# PCI_Express_16765X6890_36PIN_Half_length.net
KiCad netlist of a schematic drawn in Altium Designer
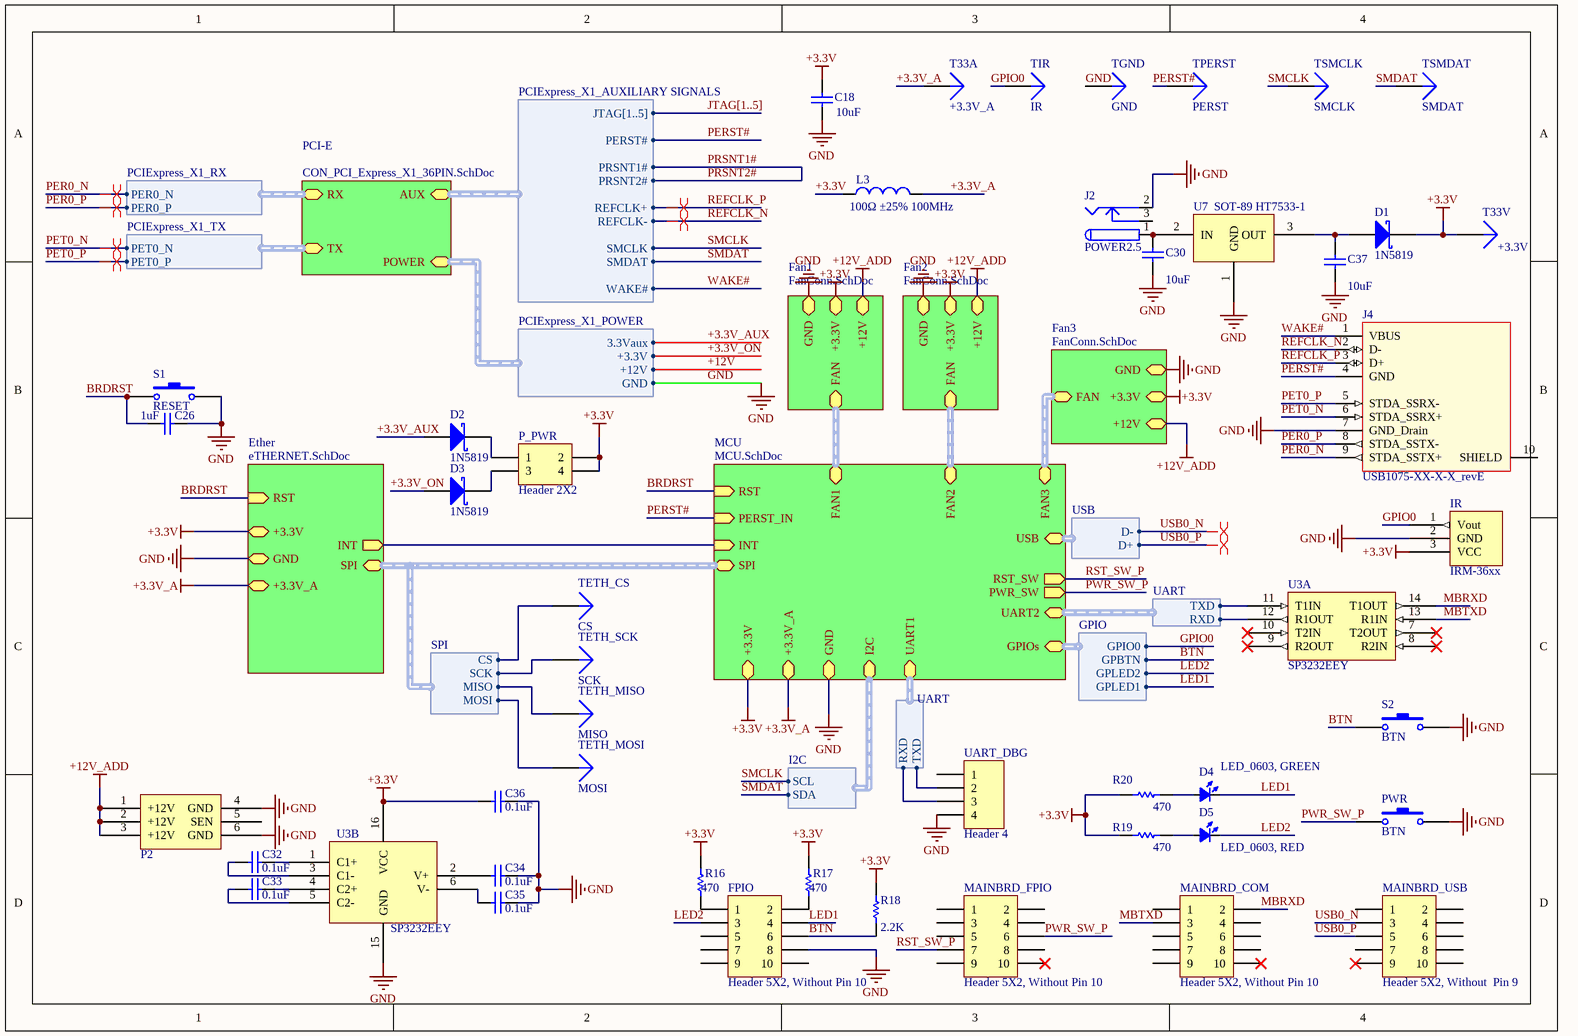
[diagram p0: PCI Express_16765X6890_36PIN_Half length.schdoc]

(export (version "E")
  (design (tool "Eeschema 10.0.6"))
  (components
    (comp (ref "C18")
      (value "10uF")
      (footprint "C-1608[0603]")
      (description "Capacitor (Semiconductor SIM Model)")
      (fields (field (name "PUBLISHER") "Altium Limited"))
      (libsource (lib "Miscellaneous Devices") (part "Cap Semi"))
    )
    (comp (ref "C26")
      (value "1uF")
      (footprint "C-1608[0603]")
      (description "Capacitor (Semiconductor SIM Model)")
      (fields (field (name "Comment") "Cap Semi") (field (name "PUBLISHER") "Altium Limited"))
      (libsource (lib "Miscellaneous Devices") (part "Cap Semi"))
    )
    (comp (ref "C30")
      (value "10uF")
      (footprint "C-1608[0603]")
      (description "Capacitor (Semiconductor SIM Model)")
      (fields (field (name "PUBLISHER") "Altium Limited"))
      (libsource (lib "Miscellaneous Devices") (part "Cap Semi"))
    )
    (comp (ref "C32")
      (value "0.1uF")
      (footprint "C-1608[0603]")
      (description "Capacitor (Semiconductor SIM Model)")
      (fields (field (name "PUBLISHER") "Altium Limited"))
      (libsource (lib "Miscellaneous Devices") (part "Cap Semi"))
    )
    (comp (ref "C33")
      (value "0.1uF")
      (footprint "C-1608[0603]")
      (description "Capacitor (Semiconductor SIM Model)")
      (fields (field (name "PUBLISHER") "Altium Limited"))
      (libsource (lib "Miscellaneous Devices") (part "Cap Semi"))
    )
    (comp (ref "C34")
      (value "0.1uF")
      (footprint "C-1608[0603]")
      (description "Capacitor (Semiconductor SIM Model)")
      (fields (field (name "PUBLISHER") "Altium Limited"))
      (libsource (lib "Miscellaneous Devices") (part "Cap Semi"))
    )
    (comp (ref "C35")
      (value "0.1uF")
      (footprint "C-1608[0603]")
      (description "Capacitor (Semiconductor SIM Model)")
      (fields (field (name "PUBLISHER") "Altium Limited"))
      (libsource (lib "Miscellaneous Devices") (part "Cap Semi"))
    )
    (comp (ref "C36")
      (value "0.1uF")
      (footprint "C-1608[0603]")
      (description "Capacitor (Semiconductor SIM Model)")
      (fields (field (name "PUBLISHER") "Altium Limited"))
      (libsource (lib "Miscellaneous Devices") (part "Cap Semi"))
    )
    (comp (ref "C37")
      (value "10uF")
      (footprint "C-1608[0603]")
      (description "Capacitor (Semiconductor SIM Model)")
      (fields (field (name "PUBLISHER") "Altium Limited"))
      (libsource (lib "Miscellaneous Devices") (part "Cap Semi"))
    )
    (comp (ref "D1")
      (value "1N5819")
      (footprint "SOD123")
      (description "Schottky Diode")
      (fields (field (name "PUBLISHER") "Altium Limited"))
      (libsource (lib "Miscellaneous Devices") (part "D Schottky"))
    )
    (comp (ref "D2")
      (value "1N5819")
      (footprint "SOD123")
      (description "Schottky Diode")
      (fields (field (name "PUBLISHER") "Altium Limited"))
      (libsource (lib "Miscellaneous Devices") (part "D Schottky"))
    )
    (comp (ref "D3")
      (value "1N5819")
      (footprint "SOD123")
      (description "Schottky Diode")
      (fields (field (name "PUBLISHER") "Altium Limited"))
      (libsource (lib "Miscellaneous Devices") (part "D Schottky"))
    )
    (comp (ref "D4")
      (value "LED_0603, GREEN")
      (footprint "PCB_ActiveLED:LED_0603_GREEN")
      (description "LED")
      (libsource (lib "SCH_Active") (part "LED_0603"))
    )
    (comp (ref "D5")
      (value "LED_0603, RED")
      (footprint "PCB_ActiveLED:LED_0603_RED")
      (description "LED")
      (libsource (lib "SCH_Active") (part "LED_0603"))
    )
    (comp (ref "FPIO")
      (value "Header 5X2, Without Pin 10")
      (footprint "HDR2X5-10")
      (description "Header, 5-Pin, Dual row")
      (fields (field (name "PUBLISHER") "Altium Limited"))
      (libsource (lib "Miscellaneous Connectors") (part "Header 5X2"))
    )
    (comp (ref "IR") (value "IRM-36xx") (footprint "IRM-36xx") (libsource (lib "general") (part "IRM-36xx")))
    (comp (ref "J2") (value "POWER2.5") (footprint "DC_POWER") (libsource (lib "general") (part "POWER2.5")))
    (comp (ref "J4")
      (value "USB1075-XX-X-X_revE")
      (footprint "USB1075-XX-X-X_revE")
      (description "USB 3.0 Receptecal, Type A, 9 Pin, Through Hole, Horizontal, Top Mount, with Kinked Shell Stakes")
      (libsource (lib "general") (part "USB1075-XX-X-X_revE"))
    )
    (comp (ref "L3")
      (value "100Ω ±25% 100MHz")
      (footprint "L-1608[0603]")
      (description "Inductor")
      (fields (field (name "PUBLISHER") "Altium Limited"))
      (libsource (lib "Miscellaneous Devices") (part "Inductor"))
    )
    (comp (ref "MAINBRD_COM")
      (value "Header 5X2, Without Pin 10")
      (footprint "HDR2X5-10")
      (description "Header, 5-Pin, Dual row")
      (fields (field (name "PUBLISHER") "Altium Limited"))
      (libsource (lib "Miscellaneous Connectors") (part "Header 5X2"))
    )
    (comp (ref "MAINBRD_FPIO")
      (value "Header 5X2, Without Pin 10")
      (footprint "HDR2X5-10")
      (description "Header, 5-Pin, Dual row")
      (fields (field (name "PUBLISHER") "Altium Limited"))
      (libsource (lib "Miscellaneous Connectors") (part "Header 5X2"))
    )
    (comp (ref "MAINBRD_USB")
      (value "Header 5X2, Without  Pin 9")
      (footprint "HDR2X5-9")
      (description "Header, 5-Pin, Dual row")
      (fields (field (name "PUBLISHER") "Altium Limited"))
      (libsource (lib "Miscellaneous Connectors") (part "Header 5X2"))
    )
    (comp (ref "P2")
      (value "PCI-E Aux Power Connector 6Pin")
      (footprint "PCIE_AUX_PWR_CONN_6P")
      (libsource (lib "general") (part "PCI-E Aux Power Connector 6Pin"))
    )
    (comp (ref "PWR")
      (value "BTN")
      (footprint "SW-SIDE")
      (description "Switch")
      (fields (field (name "PUBLISHER") "Altium Limited"))
      (libsource (lib "Miscellaneous Devices") (part "SW-PB"))
    )
    (comp (ref "P_PWR")
      (value "Header 2X2")
      (footprint "HDR2X2")
      (description "Header, 2-Pin, Dual row")
      (fields (field (name "PUBLISHER") "Altium Limited"))
      (libsource (lib "Miscellaneous Connectors") (part "Header 2X2"))
    )
    (comp (ref "R16")
      (value "470")
      (footprint "R-1608[0603]")
      (description "Semiconductor Resistor")
      (fields (field (name "PUBLISHER") "Altium Limited"))
      (libsource (lib "Miscellaneous Devices") (part "Res Semi"))
    )
    (comp (ref "R17")
      (value "470")
      (footprint "R-1608[0603]")
      (description "Semiconductor Resistor")
      (fields (field (name "PUBLISHER") "Altium Limited"))
      (libsource (lib "Miscellaneous Devices") (part "Res Semi"))
    )
    (comp (ref "R18")
      (value "2.2K")
      (footprint "R-1608[0603]")
      (description "Semiconductor Resistor")
      (fields (field (name "PUBLISHER") "Altium Limited"))
      (libsource (lib "Miscellaneous Devices") (part "Res Semi"))
    )
    (comp (ref "R19")
      (value "470")
      (footprint "R-1608[0603]")
      (description "Semiconductor Resistor")
      (fields (field (name "PUBLISHER") "Altium Limited"))
      (libsource (lib "Miscellaneous Devices") (part "Res Semi"))
    )
    (comp (ref "R20")
      (value "470")
      (footprint "R-1608[0603]")
      (description "Semiconductor Resistor")
      (fields (field (name "PUBLISHER") "Altium Limited"))
      (libsource (lib "Miscellaneous Devices") (part "Res Semi"))
    )
    (comp (ref "S1")
      (value "RESET")
      (footprint "SW-2pin-SMD")
      (description "Switch")
      (fields (field (name "PUBLISHER") "Altium Limited"))
      (libsource (lib "Miscellaneous Devices") (part "SW-PB"))
    )
    (comp (ref "S2")
      (value "BTN")
      (footprint "SW-SIDE")
      (description "Switch")
      (fields (field (name "PUBLISHER") "Altium Limited"))
      (libsource (lib "Miscellaneous Devices") (part "SW-PB"))
    )
    (comp (ref "T33A")
      (value "+3.3V_A")
      (footprint "general:TESTPOINT")
      (description "Plug")
      (fields (field (name "PUBLISHER") "Altium Limited"))
      (libsource (lib "Miscellaneous Connectors") (part "Plug"))
    )
    (comp (ref "T33V")
      (value "+3.3V")
      (footprint "general:TESTPOINT")
      (description "Plug")
      (fields (field (name "PUBLISHER") "Altium Limited"))
      (libsource (lib "Miscellaneous Connectors") (part "Plug"))
    )
    (comp (ref "TETH_CS")
      (value "CS")
      (footprint "general:TESTPOINT")
      (description "Plug")
      (fields (field (name "PUBLISHER") "Altium Limited"))
      (libsource (lib "Miscellaneous Connectors") (part "Plug"))
    )
    (comp (ref "TETH_MISO")
      (value "MISO")
      (footprint "general:TESTPOINT")
      (description "Plug")
      (fields (field (name "PUBLISHER") "Altium Limited"))
      (libsource (lib "Miscellaneous Connectors") (part "Plug"))
    )
    (comp (ref "TETH_MOSI")
      (value "MOSI")
      (footprint "general:TESTPOINT")
      (description "Plug")
      (fields (field (name "PUBLISHER") "Altium Limited"))
      (libsource (lib "Miscellaneous Connectors") (part "Plug"))
    )
    (comp (ref "TETH_SCK")
      (value "SCK")
      (footprint "general:TESTPOINT")
      (description "Plug")
      (fields (field (name "PUBLISHER") "Altium Limited"))
      (libsource (lib "Miscellaneous Connectors") (part "Plug"))
    )
    (comp (ref "TGND")
      (value "GND")
      (footprint "general:TESTPOINT")
      (description "Plug")
      (fields (field (name "PUBLISHER") "Altium Limited"))
      (libsource (lib "Miscellaneous Connectors") (part "Plug"))
    )
    (comp (ref "TIR")
      (value "IR")
      (footprint "general:TESTPOINT")
      (description "Plug")
      (fields (field (name "PUBLISHER") "Altium Limited"))
      (libsource (lib "Miscellaneous Connectors") (part "Plug"))
    )
    (comp (ref "TPERST")
      (value "PERST")
      (footprint "general:TESTPOINT")
      (description "Plug")
      (fields (field (name "PUBLISHER") "Altium Limited"))
      (libsource (lib "Miscellaneous Connectors") (part "Plug"))
    )
    (comp (ref "TSMCLK")
      (value "SMCLK")
      (footprint "general:TESTPOINT")
      (description "Plug")
      (fields (field (name "PUBLISHER") "Altium Limited"))
      (libsource (lib "Miscellaneous Connectors") (part "Plug"))
    )
    (comp (ref "TSMDAT")
      (value "SMDAT")
      (footprint "general:TESTPOINT")
      (description "Plug")
      (fields (field (name "PUBLISHER") "Altium Limited"))
      (libsource (lib "Miscellaneous Connectors") (part "Plug"))
    )
    (comp (ref "U3")
      (value "SP3232EEY")
      (footprint "LC-TSSOP-16")
      (libsource (lib "general") (part "SP3232EEY"))
    )
    (comp (ref "U7")
      (value "SOT-89 HT7533-1")
      (footprint "SOT89")
      (description "Low Power Consumption LDO")
      (libsource (lib "general") (part "HT73XX"))
    )
    (comp (ref "UART_DBG")
      (value "Header 4")
      (footprint "HDR1X4")
      (description "Header, 4-Pin")
      (fields (field (name "PUBLISHER") "Altium Limited"))
      (libsource (lib "Miscellaneous Connectors") (part "Header 4"))
    )
  )
  (nets
    (net (code "10") (name "+3.3V") (class "Default")
      (node (ref "C18") (pin "2") (pinfunction "2_2") (pintype "passive"))
      (node (ref "C36") (pin "2") (pinfunction "2_2") (pintype "passive"))
      (node (ref "D1") (pin "2") (pinfunction "K_2") (pintype "passive"))
      (node (ref "IR") (pin "3") (pinfunction "VCC_3") (pintype "power_in"))
      (node (ref "L3") (pin "1") (pinfunction "1_1") (pintype "passive"))
      (node (ref "P_PWR") (pin "2") (pinfunction "2_2") (pintype "passive"))
      (node (ref "P_PWR") (pin "4") (pinfunction "4_4") (pintype "passive"))
      (node (ref "R16") (pin "2") (pinfunction "2_2") (pintype "passive"))
      (node (ref "R17") (pin "2") (pinfunction "2_2") (pintype "passive"))
      (node (ref "R18") (pin "2") (pinfunction "2_2") (pintype "passive"))
      (node (ref "R19") (pin "2") (pinfunction "2_2") (pintype "passive"))
      (node (ref "R20") (pin "2") (pinfunction "2_2") (pintype "passive"))
      (node (ref "T33V") (pin "1") (pinfunction "1_1") (pintype "passive"))
      (node (ref "U3") (pin "16") (pinfunction "VCC_16") (pintype "power_in"))
    )
    (net (code "11") (name "+3.3V_A") (class "Default")
      (node (ref "L3") (pin "2") (pinfunction "2_2") (pintype "passive"))
      (node (ref "T33A") (pin "1") (pinfunction "1_1") (pintype "passive"))
    )
    (net (code "12") (name "+12V_ADD") (class "Default")
      (node (ref "P2") (pin "1") (pinfunction "+12V_1") (pintype "power_in"))
      (node (ref "P2") (pin "2") (pinfunction "+12V_2") (pintype "power_in"))
      (node (ref "P2") (pin "3") (pinfunction "+12V_3") (pintype "power_in"))
    )
    (net (code "13") (name "/+3.3V_AUX") (class "Default")
      (node (ref "D2") (pin "1") (pinfunction "A_1") (pintype "passive"))
    )
    (net (code "14") (name "/+3.3V_ON") (class "Default")
      (node (ref "D3") (pin "1") (pinfunction "A_1") (pintype "passive"))
    )
    (net (code "17") (name "/BRDRST") (class "Default")
      (node (ref "C26") (pin "1") (pinfunction "1_1") (pintype "passive"))
      (node (ref "S1") (pin "1") (pinfunction "1_1") (pintype "passive"))
    )
    (net (code "18") (name "/BTN") (class "Default")
      (node (ref "FPIO") (pin "6") (pinfunction "6_6") (pintype "passive"))
      (node (ref "R18") (pin "1") (pinfunction "1_1") (pintype "passive"))
      (node (ref "S2") (pin "1") (pinfunction "1_1") (pintype "passive"))
    )
    (net (code "19") (name "/CS") (class "Default")
      (node (ref "TETH_CS") (pin "1") (pinfunction "1_1") (pintype "passive"))
    )
    (net (code "23") (name "/GPIO0") (class "Default")
      (node (ref "IR") (pin "1") (pinfunction "Vout_1") (pintype "output"))
      (node (ref "TIR") (pin "1") (pinfunction "1_1") (pintype "passive"))
    )
    (net (code "25") (name "/LED1") (class "Default")
      (node (ref "D4") (pin "2") (pinfunction "K_2") (pintype "passive"))
      (node (ref "FPIO") (pin "4") (pinfunction "4_4") (pintype "passive"))
    )
    (net (code "26") (name "/LED2") (class "Default")
      (node (ref "D5") (pin "2") (pinfunction "K_2") (pintype "passive"))
      (node (ref "FPIO") (pin "3") (pinfunction "3_3") (pintype "passive"))
    )
    (net (code "27") (name "/MBRXD") (class "Default")
      (node (ref "MAINBRD_COM") (pin "2") (pinfunction "2_2") (pintype "passive"))
      (node (ref "U3") (pin "14") (pinfunction "T1OUT_14") (pintype "output"))
    )
    (net (code "28") (name "/MBTXD") (class "Default")
      (node (ref "MAINBRD_COM") (pin "3") (pinfunction "3_3") (pintype "passive"))
      (node (ref "U3") (pin "13") (pinfunction "R1IN_13") (pintype "input"))
    )
    (net (code "29") (name "/MISO") (class "Default")
      (node (ref "TETH_MISO") (pin "1") (pinfunction "1_1") (pintype "passive"))
    )
    (net (code "30") (name "/MOSI") (class "Default")
      (node (ref "TETH_MOSI") (pin "1") (pinfunction "1_1") (pintype "passive"))
    )
    (net (code "31") (name "/PER0_N") (class "Default")
      (node (ref "J4") (pin "9") (pinfunction "STDA_SSTX+_9") (pintype "output"))
    )
    (net (code "32") (name "/PER0_P") (class "Default")
      (node (ref "J4") (pin "8") (pinfunction "STDA_SSTX-_8") (pintype "output"))
    )
    (net (code "33") (name "/PERST#") (class "Default")
      (node (ref "J4") (pin "4") (pinfunction "GND_4") (pintype "power_in"))
      (node (ref "TPERST") (pin "1") (pinfunction "1_1") (pintype "passive"))
    )
    (net (code "34") (name "/PET0_N") (class "Default")
      (node (ref "J4") (pin "6") (pinfunction "STDA_SSRX+_6") (pintype "input"))
    )
    (net (code "35") (name "/PET0_P") (class "Default")
      (node (ref "J4") (pin "5") (pinfunction "STDA_SSRX-_5") (pintype "input"))
    )
    (net (code "37") (name "/PWR_SW_P") (class "Default")
      (node (ref "MAINBRD_FPIO") (pin "6") (pinfunction "6_6") (pintype "passive"))
      (node (ref "PWR") (pin "1") (pinfunction "1_1") (pintype "passive"))
    )
    (net (code "38") (name "/REFCLK_N") (class "Default")
      (node (ref "J4") (pin "2") (pinfunction "D-_2") (pintype "bidirectional"))
    )
    (net (code "39") (name "/REFCLK_P") (class "Default")
      (node (ref "J4") (pin "3") (pinfunction "D+_3") (pintype "bidirectional"))
    )
    (net (code "40") (name "/RST_SW_P") (class "Default")
      (node (ref "MAINBRD_FPIO") (pin "7") (pinfunction "7_7") (pintype "passive"))
    )
    (net (code "41") (name "/SCK") (class "Default")
      (node (ref "TETH_SCK") (pin "1") (pinfunction "1_1") (pintype "passive"))
    )
    (net (code "42") (name "/SMCLK") (class "Default")
      (node (ref "TSMCLK") (pin "1") (pinfunction "1_1") (pintype "passive"))
    )
    (net (code "43") (name "/SMDAT") (class "Default")
      (node (ref "TSMDAT") (pin "1") (pinfunction "1_1") (pintype "passive"))
    )
    (net (code "45") (name "/USB0_N") (class "Default")
      (node (ref "MAINBRD_USB") (pin "3") (pinfunction "3_3") (pintype "passive"))
    )
    (net (code "46") (name "/USB0_P") (class "Default")
      (node (ref "MAINBRD_USB") (pin "5") (pinfunction "5_5") (pintype "passive"))
    )
    (net (code "47") (name "/WAKE#") (class "Default")
      (node (ref "J4") (pin "1") (pinfunction "VBUS_1") (pintype "power_in"))
    )
    (net (code "57") (name "GND") (class "Default")
      (node (ref "C18") (pin "1") (pinfunction "1_1") (pintype "passive"))
      (node (ref "C26") (pin "2") (pinfunction "2_2") (pintype "passive"))
      (node (ref "C30") (pin "1") (pinfunction "1_1") (pintype "passive"))
      (node (ref "C34") (pin "1") (pinfunction "1_1") (pintype "passive"))
      (node (ref "C35") (pin "1") (pinfunction "1_1") (pintype "passive"))
      (node (ref "C36") (pin "1") (pinfunction "1_1") (pintype "passive"))
      (node (ref "C37") (pin "1") (pinfunction "1_1") (pintype "passive"))
      (node (ref "FPIO") (pin "8") (pinfunction "8_8") (pintype "passive"))
      (node (ref "IR") (pin "2") (pinfunction "GND_2") (pintype "power_in"))
      (node (ref "J2") (pin "2") (pintype "passive"))
      (node (ref "J4") (pin "7") (pinfunction "GND_Drain_7") (pintype "power_in"))
      (node (ref "P2") (pin "4") (pinfunction "GND_4") (pintype "power_in"))
      (node (ref "P2") (pin "6") (pinfunction "GND_6") (pintype "power_in"))
      (node (ref "PWR") (pin "2") (pinfunction "2_2") (pintype "passive"))
      (node (ref "S1") (pin "2") (pinfunction "2_2") (pintype "passive"))
      (node (ref "S2") (pin "2") (pinfunction "2_2") (pintype "passive"))
      (node (ref "TGND") (pin "1") (pinfunction "1_1") (pintype "passive"))
      (node (ref "U3") (pin "15") (pinfunction "GND_15") (pintype "power_in"))
      (node (ref "U7") (pin "1") (pinfunction "GND_1") (pintype "passive"))
      (node (ref "UART_DBG") (pin "4") (pinfunction "4_4") (pintype "passive"))
    )
    (net (code "58") (name "Net-(D1-A)") (class "Default")
      (node (ref "C37") (pin "2") (pinfunction "2_2") (pintype "passive"))
      (node (ref "D1") (pin "1") (pinfunction "A_1") (pintype "passive"))
      (node (ref "U7") (pin "3") (pinfunction "OUT_3") (pintype "passive"))
    )
    (net (code "59") (name "Net-(D2-K)") (class "Default")
      (node (ref "D2") (pin "2") (pinfunction "K_2") (pintype "passive"))
      (node (ref "P_PWR") (pin "1") (pinfunction "1_1") (pintype "passive"))
    )
    (net (code "60") (name "Net-(D3-K)") (class "Default")
      (node (ref "D3") (pin "2") (pinfunction "K_2") (pintype "passive"))
      (node (ref "P_PWR") (pin "3") (pinfunction "3_3") (pintype "passive"))
    )
    (net (code "61") (name "Net-(D4-A)") (class "Default")
      (node (ref "D4") (pin "1") (pinfunction "A_1") (pintype "passive"))
      (node (ref "R20") (pin "1") (pinfunction "1_1") (pintype "passive"))
    )
    (net (code "62") (name "Net-(D5-A)") (class "Default")
      (node (ref "D5") (pin "1") (pinfunction "A_1") (pintype "passive"))
      (node (ref "R19") (pin "1") (pinfunction "1_1") (pintype "passive"))
    )
    (net (code "63") (name "Net-(FPIO-Pad1)") (class "Default")
      (node (ref "FPIO") (pin "1") (pinfunction "1_1") (pintype "passive"))
      (node (ref "R16") (pin "1") (pinfunction "1_1") (pintype "passive"))
    )
    (net (code "64") (name "Net-(FPIO-Pad2)") (class "Default")
      (node (ref "FPIO") (pin "2") (pinfunction "2_2") (pintype "passive"))
      (node (ref "R17") (pin "1") (pinfunction "1_1") (pintype "passive"))
    )
    (net (code "65") (name "Net-(U3B-C1+)") (class "Default")
      (node (ref "C32") (pin "1") (pinfunction "1_1") (pintype "passive"))
      (node (ref "U3") (pin "1") (pinfunction "C1+_1") (pintype "power_in"))
    )
    (net (code "66") (name "Net-(U3B-C1-)") (class "Default")
      (node (ref "C32") (pin "2") (pinfunction "2_2") (pintype "passive"))
      (node (ref "U3") (pin "3") (pinfunction "C1-_3") (pintype "power_in"))
    )
    (net (code "67") (name "Net-(U3B-C2+)") (class "Default")
      (node (ref "C33") (pin "1") (pinfunction "1_1") (pintype "passive"))
      (node (ref "U3") (pin "4") (pinfunction "C2+_4") (pintype "power_in"))
    )
    (net (code "68") (name "Net-(U3B-C2-)") (class "Default")
      (node (ref "C33") (pin "2") (pinfunction "2_2") (pintype "passive"))
      (node (ref "U3") (pin "5") (pinfunction "C2-_5") (pintype "power_in"))
    )
    (net (code "69") (name "Net-(U3B-V+)") (class "Default")
      (node (ref "C34") (pin "2") (pinfunction "2_2") (pintype "passive"))
      (node (ref "U3") (pin "2") (pinfunction "V+_2") (pintype "power_in"))
    )
    (net (code "70") (name "Net-(U3B-V-)") (class "Default")
      (node (ref "C35") (pin "2") (pinfunction "2_2") (pintype "passive"))
      (node (ref "U3") (pin "6") (pinfunction "V-_6") (pintype "power_in"))
    )
    (net (code "71") (name "Net-(U7-IN)") (class "Default")
      (node (ref "C30") (pin "2") (pinfunction "2_2") (pintype "passive"))
      (node (ref "J2") (pin "1") (pintype "passive"))
      (node (ref "U7") (pin "2") (pinfunction "IN_2") (pintype "passive"))
    )
    (net (code "72") (name "unconnected-(FPIO-Pad5)") (class "Default")
      (node (ref "FPIO") (pin "5") (pinfunction "5_5") (pintype "passive"))
    )
    (net (code "73") (name "unconnected-(FPIO-Pad7)") (class "Default")
      (node (ref "FPIO") (pin "7") (pinfunction "7_7") (pintype "passive"))
    )
    (net (code "74") (name "unconnected-(FPIO-Pad9)") (class "Default")
      (node (ref "FPIO") (pin "9") (pinfunction "9_9") (pintype "passive"))
    )
    (net (code "75") (name "unconnected-(FPIO-Pad10)") (class "Default")
      (node (ref "FPIO") (pin "10") (pinfunction "10_10") (pintype "passive"))
    )
    (net (code "76") (name "unconnected-(J2-Pad3)") (class "Default")
      (node (ref "J2") (pin "3") (pintype "passive"))
    )
    (net (code "77") (name "unconnected-(J4-SHIELD-Pad10)") (class "Default")
      (node (ref "J4") (pin "10") (pinfunction "SHIELD_10") (pintype "passive"))
    )
    (net (code "78") (name "unconnected-(MAINBRD_COM-Pad1)") (class "Default")
      (node (ref "MAINBRD_COM") (pin "1") (pinfunction "1_1") (pintype "passive"))
    )
    (net (code "79") (name "unconnected-(MAINBRD_COM-Pad4)") (class "Default")
      (node (ref "MAINBRD_COM") (pin "4") (pinfunction "4_4") (pintype "passive"))
    )
    (net (code "80") (name "unconnected-(MAINBRD_COM-Pad5)") (class "Default")
      (node (ref "MAINBRD_COM") (pin "5") (pinfunction "5_5") (pintype "passive"))
    )
    (net (code "81") (name "unconnected-(MAINBRD_COM-Pad6)") (class "Default")
      (node (ref "MAINBRD_COM") (pin "6") (pinfunction "6_6") (pintype "passive"))
    )
    (net (code "82") (name "unconnected-(MAINBRD_COM-Pad7)") (class "Default")
      (node (ref "MAINBRD_COM") (pin "7") (pinfunction "7_7") (pintype "passive"))
    )
    (net (code "83") (name "unconnected-(MAINBRD_COM-Pad8)") (class "Default")
      (node (ref "MAINBRD_COM") (pin "8") (pinfunction "8_8") (pintype "passive"))
    )
    (net (code "84") (name "unconnected-(MAINBRD_COM-Pad9)") (class "Default")
      (node (ref "MAINBRD_COM") (pin "9") (pinfunction "9_9") (pintype "passive"))
    )
    (net (code "85") (name "unconnected-(MAINBRD_COM-Pad10)") (class "Default")
      (node (ref "MAINBRD_COM") (pin "10") (pinfunction "10_10") (pintype "passive+no_connect"))
    )
    (net (code "86") (name "unconnected-(MAINBRD_FPIO-Pad1)") (class "Default")
      (node (ref "MAINBRD_FPIO") (pin "1") (pinfunction "1_1") (pintype "passive"))
    )
    (net (code "87") (name "unconnected-(MAINBRD_FPIO-Pad2)") (class "Default")
      (node (ref "MAINBRD_FPIO") (pin "2") (pinfunction "2_2") (pintype "passive"))
    )
    (net (code "88") (name "unconnected-(MAINBRD_FPIO-Pad3)") (class "Default")
      (node (ref "MAINBRD_FPIO") (pin "3") (pinfunction "3_3") (pintype "passive"))
    )
    (net (code "89") (name "unconnected-(MAINBRD_FPIO-Pad4)") (class "Default")
      (node (ref "MAINBRD_FPIO") (pin "4") (pinfunction "4_4") (pintype "passive"))
    )
    (net (code "90") (name "unconnected-(MAINBRD_FPIO-Pad5)") (class "Default")
      (node (ref "MAINBRD_FPIO") (pin "5") (pinfunction "5_5") (pintype "passive"))
    )
    (net (code "91") (name "unconnected-(MAINBRD_FPIO-Pad8)") (class "Default")
      (node (ref "MAINBRD_FPIO") (pin "8") (pinfunction "8_8") (pintype "passive"))
    )
    (net (code "92") (name "unconnected-(MAINBRD_FPIO-Pad9)") (class "Default")
      (node (ref "MAINBRD_FPIO") (pin "9") (pinfunction "9_9") (pintype "passive"))
    )
    (net (code "93") (name "unconnected-(MAINBRD_FPIO-Pad10)") (class "Default")
      (node (ref "MAINBRD_FPIO") (pin "10") (pinfunction "10_10") (pintype "passive+no_connect"))
    )
    (net (code "94") (name "unconnected-(MAINBRD_USB-Pad1)") (class "Default")
      (node (ref "MAINBRD_USB") (pin "1") (pinfunction "1_1") (pintype "passive"))
    )
    (net (code "95") (name "unconnected-(MAINBRD_USB-Pad2)") (class "Default")
      (node (ref "MAINBRD_USB") (pin "2") (pinfunction "2_2") (pintype "passive"))
    )
    (net (code "96") (name "unconnected-(MAINBRD_USB-Pad4)") (class "Default")
      (node (ref "MAINBRD_USB") (pin "4") (pinfunction "4_4") (pintype "passive"))
    )
    (net (code "97") (name "unconnected-(MAINBRD_USB-Pad6)") (class "Default")
      (node (ref "MAINBRD_USB") (pin "6") (pinfunction "6_6") (pintype "passive"))
    )
    (net (code "98") (name "unconnected-(MAINBRD_USB-Pad7)") (class "Default")
      (node (ref "MAINBRD_USB") (pin "7") (pinfunction "7_7") (pintype "passive"))
    )
    (net (code "99") (name "unconnected-(MAINBRD_USB-Pad8)") (class "Default")
      (node (ref "MAINBRD_USB") (pin "8") (pinfunction "8_8") (pintype "passive"))
    )
    (net (code "100") (name "unconnected-(MAINBRD_USB-Pad9)") (class "Default")
      (node (ref "MAINBRD_USB") (pin "9") (pinfunction "9_9") (pintype "passive+no_connect"))
    )
    (net (code "101") (name "unconnected-(MAINBRD_USB-Pad10)") (class "Default")
      (node (ref "MAINBRD_USB") (pin "10") (pinfunction "10_10") (pintype "passive"))
    )
    (net (code "102") (name "unconnected-(P2-SEN-Pad5)") (class "Default")
      (node (ref "P2") (pin "5") (pinfunction "SEN_5") (pintype "power_in"))
    )
    (net (code "103") (name "unconnected-(U3A-R1OUT-Pad12)") (class "Default")
      (node (ref "U3") (pin "12") (pinfunction "R1OUT_12") (pintype "output"))
    )
    (net (code "104") (name "unconnected-(U3A-R2IN-Pad8)") (class "Default")
      (node (ref "U3") (pin "8") (pinfunction "R2IN_8") (pintype "input+no_connect"))
    )
    (net (code "105") (name "unconnected-(U3A-R2OUT-Pad9)") (class "Default")
      (node (ref "U3") (pin "9") (pinfunction "R2OUT_9") (pintype "output+no_connect"))
    )
    (net (code "106") (name "unconnected-(U3A-T1IN-Pad11)") (class "Default")
      (node (ref "U3") (pin "11") (pinfunction "T1IN_11") (pintype "input"))
    )
    (net (code "107") (name "unconnected-(U3A-T2IN-Pad10)") (class "Default")
      (node (ref "U3") (pin "10") (pinfunction "T2IN_10") (pintype "input+no_connect"))
    )
    (net (code "108") (name "unconnected-(U3A-T2OUT-Pad7)") (class "Default")
      (node (ref "U3") (pin "7") (pinfunction "T2OUT_7") (pintype "output+no_connect"))
    )
    (net (code "109") (name "unconnected-(UART_DBG-Pad1)") (class "Default")
      (node (ref "UART_DBG") (pin "1") (pinfunction "1_1") (pintype "passive"))
    )
    (net (code "110") (name "unconnected-(UART_DBG-Pad2)") (class "Default")
      (node (ref "UART_DBG") (pin "2") (pinfunction "2_2") (pintype "passive"))
    )
    (net (code "111") (name "unconnected-(UART_DBG-Pad3)") (class "Default")
      (node (ref "UART_DBG") (pin "3") (pinfunction "3_3") (pintype "passive"))
    )
  )
)
